# Sheet1.net
KiCad netlist of a schematic drawn in Altium Designer
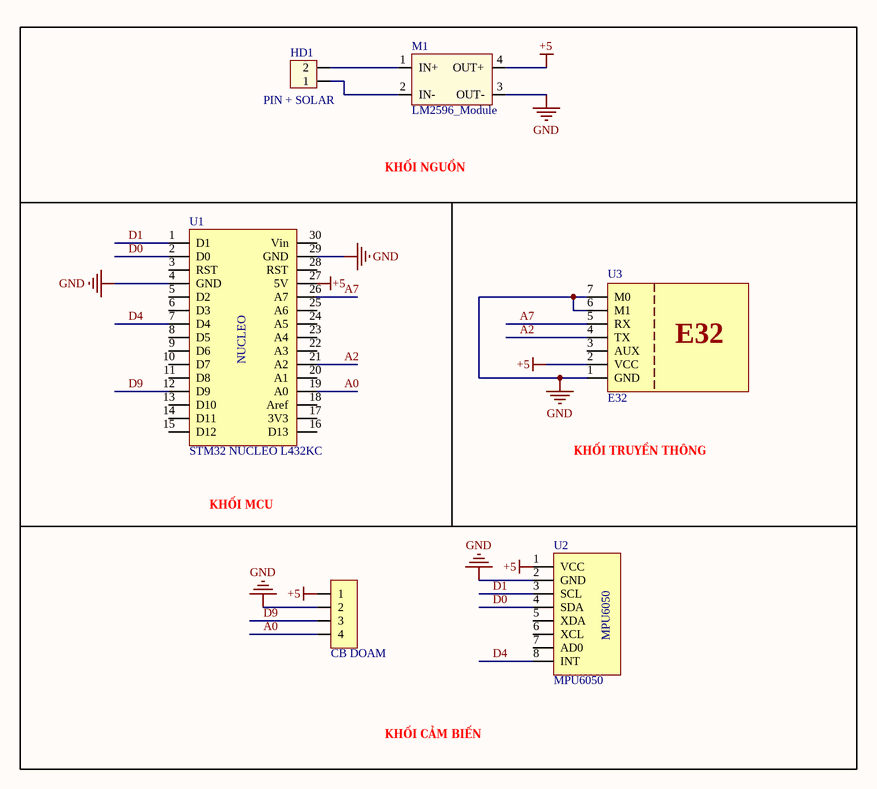
[diagram p0: Sheet1.SchDoc]

(export (version "E")
  (design (tool "Eeschema 10.0.6"))
  (components
    (comp (ref "HD1")
      (value "PIN + SOLAR")
      (footprint "HED2")
      (description "Header 2 (Green)")
      (libsource (lib "Thuvien3D") (part "Hed2"))
    )
    (comp (ref "JP1")
      (value "CB DOAM")
      (footprint "JP 1x4 CC")
      (description "Cắm")
      (libsource (lib "Altium_Lib_by_KhueNguyenCreator") (part "JP 1x4 2.54 Cai Cong"))
    )
    (comp (ref "M1")
      (value "LM2596_Module")
      (footprint "LM2596S_Module")
      (description "Module")
      (libsource (lib "SE_Altium_LIB") (part "LM2596_Module"))
    )
    (comp (ref "U1")
      (value "STM32 NUCLEO L432KC")
      (footprint "STM32 NUCLEO L432KC")
      (libsource (lib "Scorer_Tran_Library") (part "STM32 NUCLEO L432KC"))
    )
    (comp (ref "U2")
      (value "MPU6050")
      (footprint "MPU6050")
      (libsource (lib "Scorer_Tran_Library") (part "MPU6050"))
    )
    (comp (ref "U3")
      (value "E32")
      (footprint "E32")
      (description "Lora")
      (libsource (lib "Scorer_Tran_Library") (part "E32"))
    )
  )
  (nets
    (net (code "1") (name "+5") (class "Default")
      (node (ref "JP1") (pin "1") (pinfunction "1_1") (pintype "passive"))
      (node (ref "M1") (pin "4") (pinfunction "OUT+_4") (pintype "passive"))
      (node (ref "U1") (pin "27") (pinfunction "5V_27") (pintype "passive"))
      (node (ref "U2") (pin "1") (pinfunction "VCC_1") (pintype "passive"))
      (node (ref "U3") (pin "2") (pinfunction "VCC_2") (pintype "passive"))
    )
    (net (code "2") (name "/A0") (class "Default")
      (node (ref "JP1") (pin "4") (pinfunction "4_4") (pintype "passive"))
      (node (ref "U1") (pin "19") (pinfunction "A0_19") (pintype "passive"))
    )
    (net (code "3") (name "/A2") (class "Default")
      (node (ref "U1") (pin "21") (pinfunction "A2_21") (pintype "passive"))
      (node (ref "U3") (pin "4") (pinfunction "TX_4") (pintype "passive"))
    )
    (net (code "4") (name "/A7") (class "Default")
      (node (ref "U1") (pin "26") (pinfunction "A7_26") (pintype "passive"))
      (node (ref "U3") (pin "5") (pinfunction "RX_5") (pintype "passive"))
    )
    (net (code "5") (name "/D0") (class "Default")
      (node (ref "U1") (pin "2") (pinfunction "D0_2") (pintype "passive"))
      (node (ref "U2") (pin "4") (pinfunction "SDA_4") (pintype "passive"))
    )
    (net (code "6") (name "/D1") (class "Default")
      (node (ref "U1") (pin "1") (pinfunction "D1_1") (pintype "passive"))
      (node (ref "U2") (pin "3") (pinfunction "SCL_3") (pintype "passive"))
    )
    (net (code "7") (name "/D4") (class "Default")
      (node (ref "U1") (pin "7") (pinfunction "D4_7") (pintype "passive"))
      (node (ref "U2") (pin "8") (pinfunction "INT_8") (pintype "passive"))
    )
    (net (code "8") (name "/D9") (class "Default")
      (node (ref "JP1") (pin "3") (pinfunction "3_3") (pintype "passive"))
      (node (ref "U1") (pin "12") (pinfunction "D9_12") (pintype "passive"))
    )
    (net (code "9") (name "GND") (class "Default")
      (node (ref "JP1") (pin "2") (pinfunction "2_2") (pintype "passive"))
      (node (ref "M1") (pin "3") (pinfunction "OUT-_3") (pintype "passive"))
      (node (ref "U1") (pin "29") (pinfunction "GND_29") (pintype "passive"))
      (node (ref "U1") (pin "4") (pinfunction "GND_4") (pintype "passive"))
      (node (ref "U2") (pin "2") (pinfunction "GND_2") (pintype "passive"))
      (node (ref "U3") (pin "1") (pinfunction "GND_1") (pintype "passive"))
      (node (ref "U3") (pin "6") (pinfunction "M1_6") (pintype "passive"))
      (node (ref "U3") (pin "7") (pinfunction "M0_7") (pintype "passive"))
    )
    (net (code "10") (name "Net-(M1-IN+)") (class "Default")
      (node (ref "HD1") (pin "2") (pinfunction "2_2") (pintype "passive"))
      (node (ref "M1") (pin "1") (pinfunction "IN+_1") (pintype "passive"))
    )
    (net (code "11") (name "Net-(M1-IN-)") (class "Default")
      (node (ref "HD1") (pin "1") (pinfunction "1_1") (pintype "passive"))
      (node (ref "M1") (pin "2") (pinfunction "IN-_2") (pintype "passive"))
    )
    (net (code "12") (name "unconnected-(U1-3V3-Pad17)") (class "Default")
      (node (ref "U1") (pin "17") (pinfunction "3V3_17") (pintype "passive"))
    )
    (net (code "13") (name "unconnected-(U1-A1-Pad20)") (class "Default")
      (node (ref "U1") (pin "20") (pinfunction "A1_20") (pintype "passive"))
    )
    (net (code "14") (name "unconnected-(U1-A3-Pad22)") (class "Default")
      (node (ref "U1") (pin "22") (pinfunction "A3_22") (pintype "passive"))
    )
    (net (code "15") (name "unconnected-(U1-A4-Pad23)") (class "Default")
      (node (ref "U1") (pin "23") (pinfunction "A4_23") (pintype "passive"))
    )
    (net (code "16") (name "unconnected-(U1-A5-Pad24)") (class "Default")
      (node (ref "U1") (pin "24") (pinfunction "A5_24") (pintype "passive"))
    )
    (net (code "17") (name "unconnected-(U1-A6-Pad25)") (class "Default")
      (node (ref "U1") (pin "25") (pinfunction "A6_25") (pintype "passive"))
    )
    (net (code "18") (name "unconnected-(U1-Aref-Pad18)") (class "Default")
      (node (ref "U1") (pin "18") (pinfunction "Aref_18") (pintype "passive"))
    )
    (net (code "19") (name "unconnected-(U1-D2-Pad5)") (class "Default")
      (node (ref "U1") (pin "5") (pinfunction "D2_5") (pintype "passive"))
    )
    (net (code "20") (name "unconnected-(U1-D3-Pad6)") (class "Default")
      (node (ref "U1") (pin "6") (pinfunction "D3_6") (pintype "passive"))
    )
    (net (code "21") (name "unconnected-(U1-D5-Pad8)") (class "Default")
      (node (ref "U1") (pin "8") (pinfunction "D5_8") (pintype "passive"))
    )
    (net (code "22") (name "unconnected-(U1-D6-Pad9)") (class "Default")
      (node (ref "U1") (pin "9") (pinfunction "D6_9") (pintype "passive"))
    )
    (net (code "23") (name "unconnected-(U1-D7-Pad10)") (class "Default")
      (node (ref "U1") (pin "10") (pinfunction "D7_10") (pintype "passive"))
    )
    (net (code "24") (name "unconnected-(U1-D8-Pad11)") (class "Default")
      (node (ref "U1") (pin "11") (pinfunction "D8_11") (pintype "passive"))
    )
    (net (code "25") (name "unconnected-(U1-D10-Pad13)") (class "Default")
      (node (ref "U1") (pin "13") (pinfunction "D10_13") (pintype "passive"))
    )
    (net (code "26") (name "unconnected-(U1-D11-Pad14)") (class "Default")
      (node (ref "U1") (pin "14") (pinfunction "D11_14") (pintype "passive"))
    )
    (net (code "27") (name "unconnected-(U1-D12-Pad15)") (class "Default")
      (node (ref "U1") (pin "15") (pinfunction "D12_15") (pintype "passive"))
    )
    (net (code "28") (name "unconnected-(U1-D13-Pad16)") (class "Default")
      (node (ref "U1") (pin "16") (pinfunction "D13_16") (pintype "passive"))
    )
    (net (code "29") (name "unconnected-(U1-RST-Pad3)") (class "Default")
      (node (ref "U1") (pin "3") (pinfunction "RST_3") (pintype "passive"))
    )
    (net (code "30") (name "unconnected-(U1-RST-Pad28)") (class "Default")
      (node (ref "U1") (pin "28") (pinfunction "RST_28") (pintype "passive"))
    )
    (net (code "31") (name "unconnected-(U1-Vin-Pad30)") (class "Default")
      (node (ref "U1") (pin "30") (pinfunction "Vin_30") (pintype "passive"))
    )
    (net (code "32") (name "unconnected-(U2-AD0-Pad7)") (class "Default")
      (node (ref "U2") (pin "7") (pinfunction "AD0_7") (pintype "passive"))
    )
    (net (code "33") (name "unconnected-(U2-XCL-Pad6)") (class "Default")
      (node (ref "U2") (pin "6") (pinfunction "XCL_6") (pintype "passive"))
    )
    (net (code "34") (name "unconnected-(U2-XDA-Pad5)") (class "Default")
      (node (ref "U2") (pin "5") (pinfunction "XDA_5") (pintype "passive"))
    )
    (net (code "35") (name "unconnected-(U3-AUX-Pad3)") (class "Default")
      (node (ref "U3") (pin "3") (pinfunction "AUX_3") (pintype "passive"))
    )
  )
)
